# BT_3860.net
KiCad netlist of a schematic drawn in EAGLE
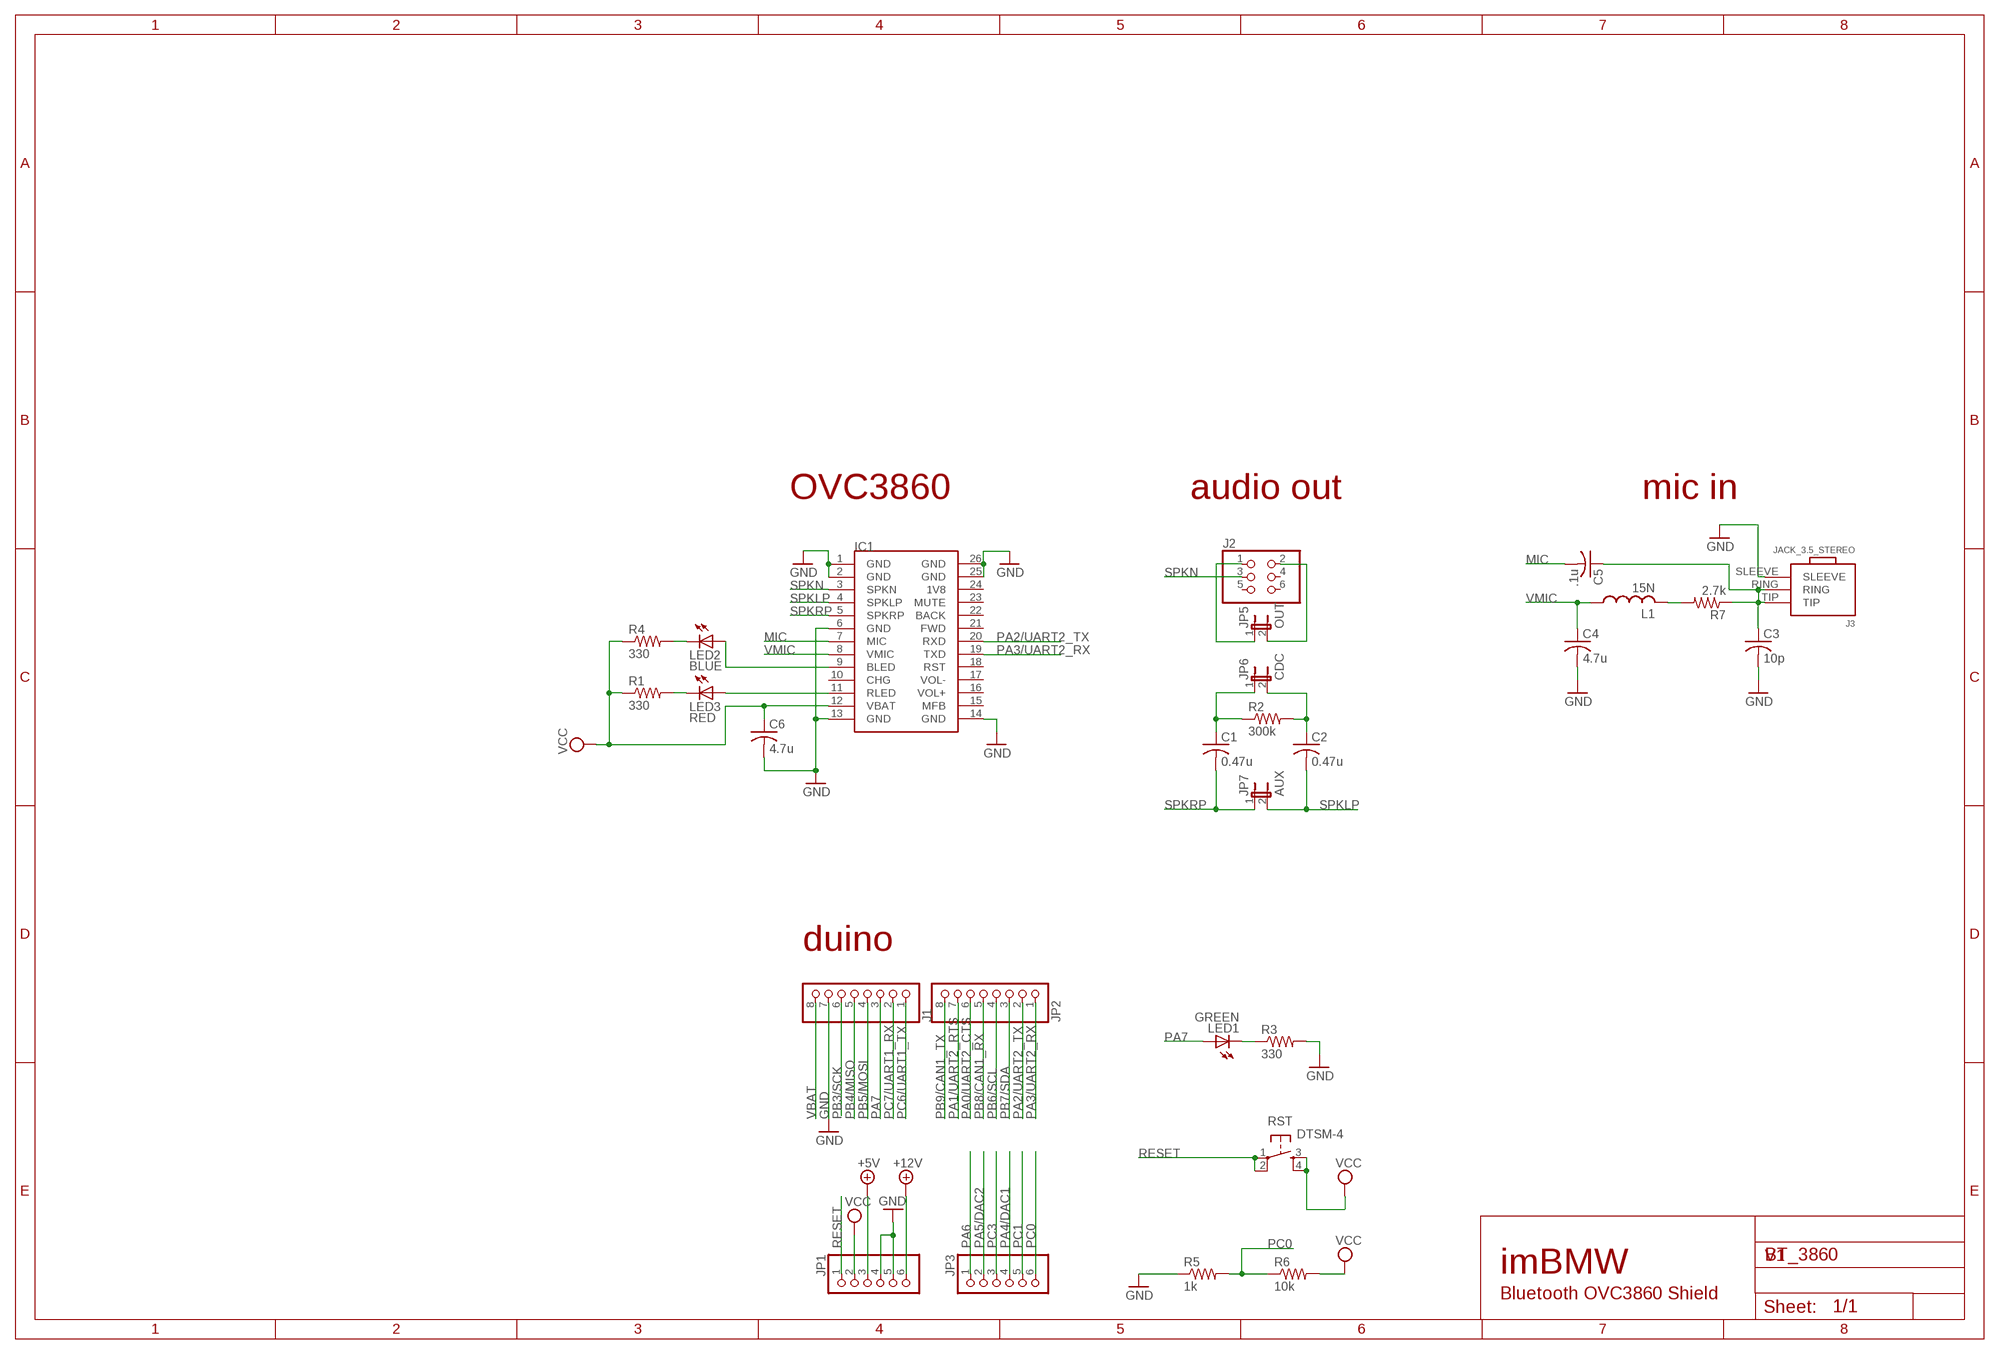
[diagram p0: schematic, sheet 1]

(export (version "E")
  (design (tool "Eeschema 10.0.6"))
  (components
    (comp (ref "C1")
      (value "0.47u")
      (footprint "eagle-import:C0805")
      (libsource (lib "eagle-import") (part "C-USC0805"))
    )
    (comp (ref "C2")
      (value "0.47u")
      (footprint "eagle-import:C0805")
      (libsource (lib "eagle-import") (part "C-USC0805"))
    )
    (comp (ref "C3")
      (value "10p")
      (footprint "eagle-import:C0805")
      (libsource (lib "eagle-import") (part "C-USC0805"))
    )
    (comp (ref "C4")
      (value "4.7u")
      (footprint "eagle-import:C0805")
      (libsource (lib "eagle-import") (part "C-USC0805"))
    )
    (comp (ref "C5")
      (value ".1u")
      (footprint "eagle-import:C0805")
      (libsource (lib "eagle-import") (part "C-USC0805"))
    )
    (comp (ref "C6")
      (value "4.7u")
      (footprint "eagle-import:C0805")
      (libsource (lib "eagle-import") (part "C-USC0805"))
    )
    (comp (ref "IC1")
      (value "BLK-MD-SPK-B")
      (footprint "eagle-import:BLK-MD-SPK-B")
      (libsource (lib "eagle-import") (part "BLK-MD-SPK-B"))
    )
    (comp (ref "J1")
      (value "PINHD-1X8")
      (footprint "eagle-import:1X08")
      (libsource (lib "eagle-import") (part "PINHD-1X8"))
    )
    (comp (ref "J2")
      (value "PINHD-2X3")
      (footprint "eagle-import:2X03")
      (libsource (lib "eagle-import") (part "PINHD-2X3"))
    )
    (comp (ref "J3")
      (value "JACK_3.5_STEREO")
      (footprint "eagle-import:JACK_3.5_STEREO")
      (libsource (lib "eagle-import") (part "JACK_3.5_STEREO"))
    )
    (comp (ref "JP1")
      (value "PINHD-1X6")
      (footprint "eagle-import:1X06")
      (libsource (lib "eagle-import") (part "PINHD-1X6"))
    )
    (comp (ref "JP2")
      (value "PINHD-1X8")
      (footprint "eagle-import:1X08")
      (libsource (lib "eagle-import") (part "PINHD-1X8"))
    )
    (comp (ref "JP3")
      (value "PINHD-1X6")
      (footprint "eagle-import:1X06")
      (libsource (lib "eagle-import") (part "PINHD-1X6"))
    )
    (comp (ref "JP5")
      (value "OUT")
      (footprint "eagle-import:JP1")
      (libsource (lib "eagle-import") (part "JP1E"))
    )
    (comp (ref "JP6")
      (value "CDC")
      (footprint "eagle-import:JP1")
      (libsource (lib "eagle-import") (part "JP1E"))
    )
    (comp (ref "JP7")
      (value "AUX")
      (footprint "eagle-import:JP1")
      (libsource (lib "eagle-import") (part "JP1E"))
    )
    (comp (ref "L1")
      (value "15N")
      (footprint "eagle-import:L3230M")
      (libsource (lib "eagle-import") (part "L-USL3230M"))
    )
    (comp (ref "LED1")
      (value "GREEN")
      (footprint "eagle-import:SML0603")
      (libsource (lib "eagle-import") (part "LEDSML0603"))
    )
    (comp (ref "LED2")
      (value "BLUE")
      (footprint "eagle-import:SML0603")
      (libsource (lib "eagle-import") (part "LEDSML0603"))
    )
    (comp (ref "LED3")
      (value "RED")
      (footprint "eagle-import:SML0603")
      (libsource (lib "eagle-import") (part "LEDSML0603"))
    )
    (comp (ref "R1")
      (value "330")
      (footprint "eagle-import:R0805")
      (libsource (lib "eagle-import") (part "R-US_R0805"))
    )
    (comp (ref "R2")
      (value "300k")
      (footprint "eagle-import:R0805")
      (libsource (lib "eagle-import") (part "R-US_R0805"))
    )
    (comp (ref "R3")
      (value "330")
      (footprint "eagle-import:R0805")
      (libsource (lib "eagle-import") (part "R-US_R0805"))
    )
    (comp (ref "R4")
      (value "330")
      (footprint "eagle-import:R0805")
      (libsource (lib "eagle-import") (part "R-US_R0805"))
    )
    (comp (ref "R5")
      (value "1k")
      (footprint "eagle-import:R0805")
      (libsource (lib "eagle-import") (part "R-US_R0805"))
    )
    (comp (ref "R6")
      (value "10k")
      (footprint "eagle-import:R0805")
      (libsource (lib "eagle-import") (part "R-US_R0805"))
    )
    (comp (ref "R7")
      (value "2.7k")
      (footprint "eagle-import:R0805")
      (libsource (lib "eagle-import") (part "R-US_R0805"))
    )
    (comp (ref "RST")
      (value "DTSM-4")
      (footprint "eagle-import:DTSM-4")
      (libsource (lib "eagle-import") (part "DTSM-4"))
    )
  )
  (nets
    (net (code "1") (name "+5V") (class "Default")
      (node (ref "JP1") (pin "3") (pinfunction "3_3") (pintype "passive"))
    )
    (net (code "2") (name "+12V") (class "Default")
      (node (ref "JP1") (pin "6") (pinfunction "6_6") (pintype "passive"))
    )
    (net (code "3") (name "/MIC") (class "Default")
      (node (ref "C5") (pin "2") (pinfunction "2_2") (pintype "passive"))
      (node (ref "IC1") (pin "7") (pinfunction "MIC_7") (pintype "bidirectional"))
    )
    (net (code "4") (name "/PA0{slash}UART2_CTS") (class "Default")
      (node (ref "JP2") (pin "6") (pinfunction "6_6") (pintype "passive"))
    )
    (net (code "5") (name "/PA1{slash}UART2_RTS") (class "Default")
      (node (ref "JP2") (pin "7") (pinfunction "7_7") (pintype "passive"))
    )
    (net (code "6") (name "/PA2{slash}UART2_TX") (class "Default")
      (node (ref "IC1") (pin "20") (pinfunction "RXD_20") (pintype "bidirectional"))
      (node (ref "JP2") (pin "2") (pinfunction "2_2") (pintype "passive"))
    )
    (net (code "7") (name "/PA3{slash}UART2_RX") (class "Default")
      (node (ref "IC1") (pin "19") (pinfunction "TXD_19") (pintype "bidirectional"))
      (node (ref "JP2") (pin "1") (pinfunction "1_1") (pintype "passive"))
    )
    (net (code "8") (name "/PA4{slash}DAC1") (class "Default")
      (node (ref "JP3") (pin "4") (pinfunction "4_4") (pintype "passive"))
    )
    (net (code "9") (name "/PA5{slash}DAC2") (class "Default")
      (node (ref "JP3") (pin "2") (pinfunction "2_2") (pintype "passive"))
    )
    (net (code "10") (name "/PA6") (class "Default")
      (node (ref "JP3") (pin "1") (pinfunction "1_1") (pintype "passive"))
    )
    (net (code "11") (name "/PA7") (class "Default")
      (node (ref "J1") (pin "3") (pinfunction "3_3") (pintype "passive"))
      (node (ref "LED1") (pin "A") (pinfunction "A_A") (pintype "passive"))
    )
    (net (code "12") (name "/PB3{slash}SCK") (class "Default")
      (node (ref "J1") (pin "6") (pinfunction "6_6") (pintype "passive"))
    )
    (net (code "13") (name "/PB4{slash}MISO") (class "Default")
      (node (ref "J1") (pin "5") (pinfunction "5_5") (pintype "passive"))
    )
    (net (code "14") (name "/PB5{slash}MOSI") (class "Default")
      (node (ref "J1") (pin "4") (pinfunction "4_4") (pintype "passive"))
    )
    (net (code "15") (name "/PB6{slash}SCL") (class "Default")
      (node (ref "JP2") (pin "4") (pinfunction "4_4") (pintype "passive"))
    )
    (net (code "16") (name "/PB7{slash}SDA") (class "Default")
      (node (ref "JP2") (pin "3") (pinfunction "3_3") (pintype "passive"))
    )
    (net (code "17") (name "/PB8{slash}CAN1_RX") (class "Default")
      (node (ref "JP2") (pin "5") (pinfunction "5_5") (pintype "passive"))
    )
    (net (code "18") (name "/PB9{slash}CAN1_TX") (class "Default")
      (node (ref "JP2") (pin "8") (pinfunction "8_8") (pintype "passive"))
    )
    (net (code "19") (name "/PC0") (class "Default")
      (node (ref "JP3") (pin "6") (pinfunction "6_6") (pintype "passive"))
      (node (ref "R5") (pin "2") (pinfunction "2_2") (pintype "passive"))
      (node (ref "R6") (pin "1") (pinfunction "1_1") (pintype "passive"))
    )
    (net (code "20") (name "/PC1") (class "Default")
      (node (ref "JP3") (pin "5") (pinfunction "5_5") (pintype "passive"))
    )
    (net (code "21") (name "/PC3") (class "Default")
      (node (ref "JP3") (pin "3") (pinfunction "3_3") (pintype "passive"))
    )
    (net (code "22") (name "/PC6{slash}UART1_TX") (class "Default")
      (node (ref "J1") (pin "1") (pinfunction "1_1") (pintype "passive"))
    )
    (net (code "23") (name "/PC7{slash}UART1_RX") (class "Default")
      (node (ref "J1") (pin "2") (pinfunction "2_2") (pintype "passive"))
    )
    (net (code "24") (name "/RESET") (class "Default")
      (node (ref "JP1") (pin "1") (pinfunction "1_1") (pintype "passive"))
      (node (ref "RST") (pin "1") (pinfunction "1_1") (pintype "passive"))
      (node (ref "RST") (pin "2") (pinfunction "2_2") (pintype "passive"))
    )
    (net (code "25") (name "/SPKLP") (class "Default")
      (node (ref "C2") (pin "2") (pinfunction "2_2") (pintype "passive"))
      (node (ref "IC1") (pin "4") (pinfunction "SPKLP_4") (pintype "bidirectional"))
      (node (ref "JP7") (pin "2") (pinfunction "2_2") (pintype "passive"))
    )
    (net (code "26") (name "/SPKN") (class "Default")
      (node (ref "IC1") (pin "3") (pinfunction "SPKN_3") (pintype "bidirectional"))
      (node (ref "J2") (pin "3") (pinfunction "3_3") (pintype "passive"))
    )
    (net (code "27") (name "/SPKRP") (class "Default")
      (node (ref "C1") (pin "2") (pinfunction "2_2") (pintype "passive"))
      (node (ref "IC1") (pin "5") (pinfunction "SPKRP_5") (pintype "bidirectional"))
      (node (ref "JP7") (pin "1") (pinfunction "1_1") (pintype "passive"))
    )
    (net (code "28") (name "/VBAT") (class "Default")
      (node (ref "J1") (pin "8") (pinfunction "8_8") (pintype "passive"))
    )
    (net (code "29") (name "/VMIC") (class "Default")
      (node (ref "C4") (pin "1") (pinfunction "1_1") (pintype "passive"))
      (node (ref "IC1") (pin "8") (pinfunction "VMIC_8") (pintype "bidirectional"))
      (node (ref "L1") (pin "1") (pinfunction "1_1") (pintype "passive"))
    )
    (net (code "30") (name "GND") (class "Default")
      (node (ref "C3") (pin "2") (pinfunction "2_2") (pintype "passive"))
      (node (ref "C4") (pin "2") (pinfunction "2_2") (pintype "passive"))
      (node (ref "C6") (pin "2") (pinfunction "2_2") (pintype "passive"))
      (node (ref "IC1") (pin "1") (pinfunction "GND_1") (pintype "bidirectional"))
      (node (ref "IC1") (pin "13") (pinfunction "GND_13") (pintype "bidirectional"))
      (node (ref "IC1") (pin "14") (pinfunction "GND_14") (pintype "bidirectional"))
      (node (ref "IC1") (pin "2") (pinfunction "GND_2") (pintype "bidirectional"))
      (node (ref "IC1") (pin "25") (pinfunction "GND_25") (pintype "bidirectional"))
      (node (ref "IC1") (pin "26") (pinfunction "GND_26") (pintype "bidirectional"))
      (node (ref "IC1") (pin "6") (pinfunction "GND_6") (pintype "bidirectional"))
      (node (ref "J1") (pin "7") (pinfunction "7_7") (pintype "passive"))
      (node (ref "J3") (pin "SLEEVE") (pinfunction "SLEEVE_SLEEVE") (pintype "bidirectional"))
      (node (ref "JP1") (pin "4") (pinfunction "4_4") (pintype "passive"))
      (node (ref "JP1") (pin "5") (pinfunction "5_5") (pintype "passive"))
      (node (ref "R3") (pin "2") (pinfunction "2_2") (pintype "passive"))
      (node (ref "R5") (pin "1") (pinfunction "1_1") (pintype "passive"))
    )
    (net (code "31") (name "Net-(C1-Pad1)") (class "Default")
      (node (ref "C1") (pin "1") (pinfunction "1_1") (pintype "passive"))
      (node (ref "JP6") (pin "1") (pinfunction "1_1") (pintype "passive"))
      (node (ref "R2") (pin "1") (pinfunction "1_1") (pintype "passive"))
    )
    (net (code "32") (name "Net-(C2-Pad1)") (class "Default")
      (node (ref "C2") (pin "1") (pinfunction "1_1") (pintype "passive"))
      (node (ref "JP6") (pin "2") (pinfunction "2_2") (pintype "passive"))
      (node (ref "R2") (pin "2") (pinfunction "2_2") (pintype "passive"))
    )
    (net (code "33") (name "Net-(C3-Pad1)") (class "Default")
      (node (ref "C3") (pin "1") (pinfunction "1_1") (pintype "passive"))
      (node (ref "C5") (pin "1") (pinfunction "1_1") (pintype "passive"))
      (node (ref "J3") (pin "RING") (pinfunction "RING_RING") (pintype "bidirectional"))
      (node (ref "J3") (pin "TIP") (pinfunction "TIP_TIP") (pintype "bidirectional"))
      (node (ref "R7") (pin "1") (pinfunction "1_1") (pintype "passive"))
    )
    (net (code "34") (name "Net-(IC1-BLED)") (class "Default")
      (node (ref "IC1") (pin "9") (pinfunction "BLED_9") (pintype "bidirectional"))
      (node (ref "LED2") (pin "A") (pinfunction "A_A") (pintype "passive"))
    )
    (net (code "35") (name "Net-(IC1-RLED)") (class "Default")
      (node (ref "IC1") (pin "11") (pinfunction "RLED_11") (pintype "bidirectional"))
      (node (ref "LED3") (pin "A") (pinfunction "A_A") (pintype "passive"))
    )
    (net (code "36") (name "Net-(J2-Pad1)") (class "Default")
      (node (ref "J2") (pin "1") (pinfunction "1_1") (pintype "passive"))
      (node (ref "JP5") (pin "1") (pinfunction "1_1") (pintype "passive"))
    )
    (net (code "37") (name "Net-(J2-Pad2)") (class "Default")
      (node (ref "J2") (pin "2") (pinfunction "2_2") (pintype "passive"))
      (node (ref "JP5") (pin "2") (pinfunction "2_2") (pintype "passive"))
    )
    (net (code "38") (name "Net-(L1-Pad2)") (class "Default")
      (node (ref "L1") (pin "2") (pinfunction "2_2") (pintype "passive"))
      (node (ref "R7") (pin "2") (pinfunction "2_2") (pintype "passive"))
    )
    (net (code "39") (name "Net-(LED1-PadC)") (class "Default")
      (node (ref "LED1") (pin "C") (pinfunction "C_C") (pintype "passive"))
      (node (ref "R3") (pin "1") (pinfunction "1_1") (pintype "passive"))
    )
    (net (code "40") (name "Net-(LED2-PadC)") (class "Default")
      (node (ref "LED2") (pin "C") (pinfunction "C_C") (pintype "passive"))
      (node (ref "R4") (pin "2") (pinfunction "2_2") (pintype "passive"))
    )
    (net (code "41") (name "Net-(LED3-PadC)") (class "Default")
      (node (ref "LED3") (pin "C") (pinfunction "C_C") (pintype "passive"))
      (node (ref "R1") (pin "2") (pinfunction "2_2") (pintype "passive"))
    )
    (net (code "42") (name "VCC") (class "Default")
      (node (ref "C6") (pin "1") (pinfunction "1_1") (pintype "passive"))
      (node (ref "IC1") (pin "12") (pinfunction "VBAT_12") (pintype "bidirectional"))
      (node (ref "JP1") (pin "2") (pinfunction "2_2") (pintype "passive"))
      (node (ref "R1") (pin "1") (pinfunction "1_1") (pintype "passive"))
      (node (ref "R4") (pin "1") (pinfunction "1_1") (pintype "passive"))
      (node (ref "R6") (pin "2") (pinfunction "2_2") (pintype "passive"))
      (node (ref "RST") (pin "3") (pinfunction "3_3") (pintype "passive"))
      (node (ref "RST") (pin "4") (pinfunction "4_4") (pintype "passive"))
    )
    (net (code "43") (name "unconnected-(IC1-1V8-Pad24)") (class "Default")
      (node (ref "IC1") (pin "24") (pinfunction "1V8_24") (pintype "bidirectional"))
    )
    (net (code "44") (name "unconnected-(IC1-BACK-Pad22)") (class "Default")
      (node (ref "IC1") (pin "22") (pinfunction "BACK_22") (pintype "bidirectional"))
    )
    (net (code "45") (name "unconnected-(IC1-CHG-Pad10)") (class "Default")
      (node (ref "IC1") (pin "10") (pinfunction "CHG_10") (pintype "bidirectional"))
    )
    (net (code "46") (name "unconnected-(IC1-FWD-Pad21)") (class "Default")
      (node (ref "IC1") (pin "21") (pinfunction "FWD_21") (pintype "bidirectional"))
    )
    (net (code "47") (name "unconnected-(IC1-MFB-Pad15)") (class "Default")
      (node (ref "IC1") (pin "15") (pinfunction "MFB_15") (pintype "bidirectional"))
    )
    (net (code "48") (name "unconnected-(IC1-MUTE-Pad23)") (class "Default")
      (node (ref "IC1") (pin "23") (pinfunction "MUTE_23") (pintype "bidirectional"))
    )
    (net (code "49") (name "unconnected-(IC1-RST-Pad18)") (class "Default")
      (node (ref "IC1") (pin "18") (pinfunction "RST_18") (pintype "bidirectional"))
    )
    (net (code "50") (name "unconnected-(IC1-VOL+-Pad16)") (class "Default")
      (node (ref "IC1") (pin "16") (pinfunction "VOL+_16") (pintype "bidirectional"))
    )
    (net (code "51") (name "unconnected-(IC1-VOL--Pad17)") (class "Default")
      (node (ref "IC1") (pin "17") (pinfunction "VOL-_17") (pintype "bidirectional"))
    )
    (net (code "52") (name "unconnected-(J2-Pad4)") (class "Default")
      (node (ref "J2") (pin "4") (pinfunction "4_4") (pintype "passive"))
    )
    (net (code "53") (name "unconnected-(J2-Pad5)") (class "Default")
      (node (ref "J2") (pin "5") (pinfunction "5_5") (pintype "passive"))
    )
    (net (code "54") (name "unconnected-(J2-Pad6)") (class "Default")
      (node (ref "J2") (pin "6") (pinfunction "6_6") (pintype "passive"))
    )
  )
)
